# Main_Circuit.net
KiCad netlist of a schematic drawn in EAGLE
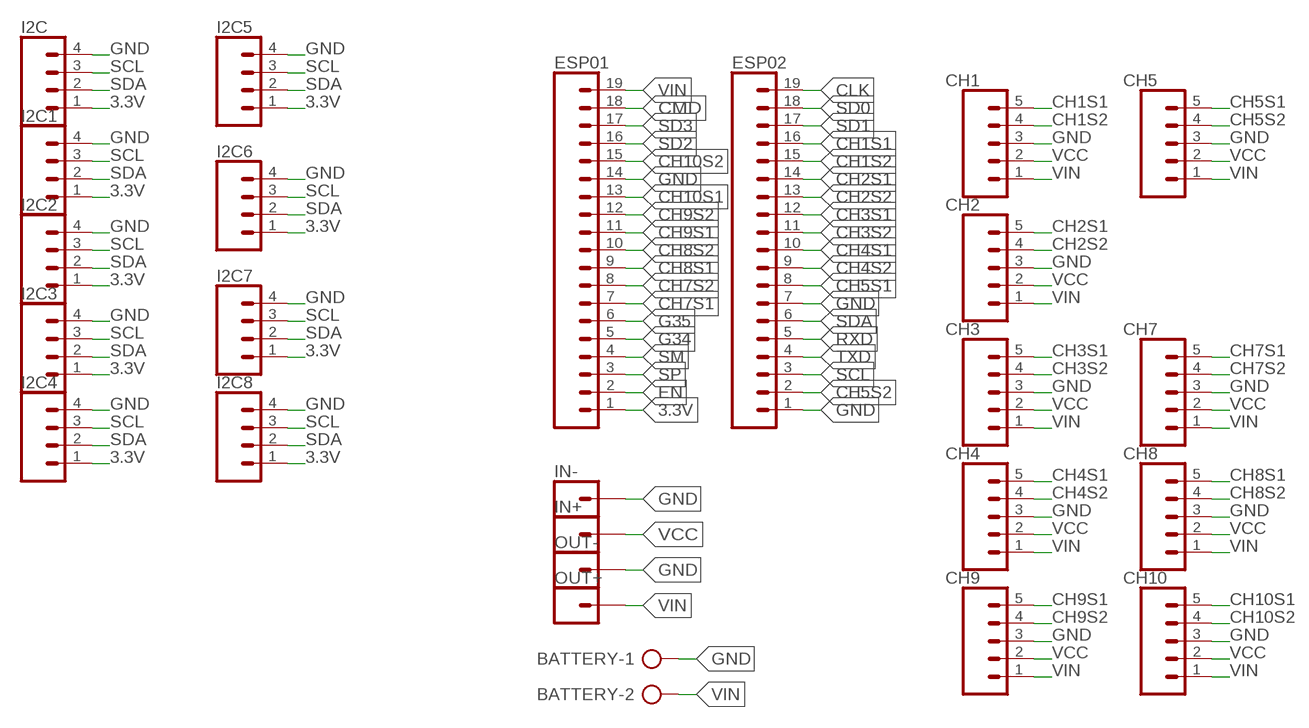
[diagram p0: schematic, sheet 1]

(export (version "E")
  (design (tool "Eeschema 10.0.6"))
  (components
    (comp (ref "BATTERY")
      (value "AK500/2-H")
      (footprint "eagle-import:AK500_2-H")
      (libsource (lib "eagle-import") (part "AK500/2-H"))
    )
    (comp (ref "CH1")
      (value "CONN_05")
      (footprint "eagle-import:1X05")
      (libsource (lib "eagle-import") (part "CONN_05"))
    )
    (comp (ref "CH2")
      (value "CONN_05")
      (footprint "eagle-import:1X05")
      (libsource (lib "eagle-import") (part "CONN_05"))
    )
    (comp (ref "CH3")
      (value "CONN_05")
      (footprint "eagle-import:1X05")
      (libsource (lib "eagle-import") (part "CONN_05"))
    )
    (comp (ref "CH4")
      (value "CONN_05")
      (footprint "eagle-import:1X05")
      (libsource (lib "eagle-import") (part "CONN_05"))
    )
    (comp (ref "CH5")
      (value "CONN_05")
      (footprint "eagle-import:1X05")
      (libsource (lib "eagle-import") (part "CONN_05"))
    )
    (comp (ref "CH7")
      (value "CONN_05")
      (footprint "eagle-import:1X05")
      (libsource (lib "eagle-import") (part "CONN_05"))
    )
    (comp (ref "CH8")
      (value "CONN_05")
      (footprint "eagle-import:1X05")
      (libsource (lib "eagle-import") (part "CONN_05"))
    )
    (comp (ref "CH9")
      (value "CONN_05")
      (footprint "eagle-import:1X05")
      (libsource (lib "eagle-import") (part "CONN_05"))
    )
    (comp (ref "CH10")
      (value "CONN_05")
      (footprint "eagle-import:1X05")
      (libsource (lib "eagle-import") (part "CONN_05"))
    )
    (comp (ref "ESP01")
      (value "CONN_19")
      (footprint "eagle-import:1X19")
      (libsource (lib "eagle-import") (part "CONN_19"))
    )
    (comp (ref "ESP02")
      (value "CONN_19")
      (footprint "eagle-import:1X19")
      (libsource (lib "eagle-import") (part "CONN_19"))
    )
    (comp (ref "I2C")
      (value "CONN_04")
      (footprint "eagle-import:1X04")
      (libsource (lib "eagle-import") (part "CONN_04"))
    )
    (comp (ref "I2C1")
      (value "CONN_04")
      (footprint "eagle-import:1X04")
      (libsource (lib "eagle-import") (part "CONN_04"))
    )
    (comp (ref "I2C2")
      (value "CONN_04")
      (footprint "eagle-import:1X04")
      (libsource (lib "eagle-import") (part "CONN_04"))
    )
    (comp (ref "I2C3")
      (value "CONN_04")
      (footprint "eagle-import:1X04")
      (libsource (lib "eagle-import") (part "CONN_04"))
    )
    (comp (ref "I2C4")
      (value "CONN_04")
      (footprint "eagle-import:1X04")
      (libsource (lib "eagle-import") (part "CONN_04"))
    )
    (comp (ref "I2C5")
      (value "CONN_04")
      (footprint "eagle-import:1X04")
      (libsource (lib "eagle-import") (part "CONN_04"))
    )
    (comp (ref "I2C6")
      (value "CONN_04")
      (footprint "eagle-import:1X04")
      (libsource (lib "eagle-import") (part "CONN_04"))
    )
    (comp (ref "I2C7")
      (value "CONN_04")
      (footprint "eagle-import:1X04")
      (libsource (lib "eagle-import") (part "CONN_04"))
    )
    (comp (ref "I2C8")
      (value "CONN_04")
      (footprint "eagle-import:1X04")
      (libsource (lib "eagle-import") (part "CONN_04"))
    )
    (comp (ref "IN+")
      (value "CONN_01")
      (footprint "eagle-import:1X01")
      (libsource (lib "eagle-import") (part "CONN_01"))
    )
    (comp (ref "IN-")
      (value "CONN_01")
      (footprint "eagle-import:1X01")
      (libsource (lib "eagle-import") (part "CONN_01"))
    )
    (comp (ref "OUT+")
      (value "CONN_01")
      (footprint "eagle-import:1X01")
      (libsource (lib "eagle-import") (part "CONN_01"))
    )
    (comp (ref "OUT-")
      (value "CONN_01")
      (footprint "eagle-import:1X01")
      (libsource (lib "eagle-import") (part "CONN_01"))
    )
  )
  (nets
    (net (code "1") (name "3.3V") (class "Default")
      (node (ref "ESP01") (pin "1") (pinfunction "1_1") (pintype "passive"))
      (node (ref "I2C") (pin "1") (pinfunction "1_1") (pintype "passive"))
      (node (ref "I2C1") (pin "1") (pinfunction "1_1") (pintype "passive"))
      (node (ref "I2C2") (pin "1") (pinfunction "1_1") (pintype "passive"))
      (node (ref "I2C3") (pin "1") (pinfunction "1_1") (pintype "passive"))
      (node (ref "I2C4") (pin "1") (pinfunction "1_1") (pintype "passive"))
      (node (ref "I2C5") (pin "1") (pinfunction "1_1") (pintype "passive"))
      (node (ref "I2C6") (pin "1") (pinfunction "1_1") (pintype "passive"))
      (node (ref "I2C7") (pin "1") (pinfunction "1_1") (pintype "passive"))
      (node (ref "I2C8") (pin "1") (pinfunction "1_1") (pintype "passive"))
    )
    (net (code "2") (name "CH1S1") (class "Default")
      (node (ref "CH1") (pin "5") (pinfunction "5_5") (pintype "passive"))
      (node (ref "ESP02") (pin "16") (pinfunction "16_16") (pintype "passive"))
    )
    (net (code "3") (name "CH1S2") (class "Default")
      (node (ref "CH1") (pin "4") (pinfunction "4_4") (pintype "passive"))
      (node (ref "ESP02") (pin "15") (pinfunction "15_15") (pintype "passive"))
    )
    (net (code "4") (name "CH2S1") (class "Default")
      (node (ref "CH2") (pin "5") (pinfunction "5_5") (pintype "passive"))
      (node (ref "ESP02") (pin "14") (pinfunction "14_14") (pintype "passive"))
    )
    (net (code "5") (name "CH2S2") (class "Default")
      (node (ref "CH2") (pin "4") (pinfunction "4_4") (pintype "passive"))
      (node (ref "ESP02") (pin "13") (pinfunction "13_13") (pintype "passive"))
    )
    (net (code "6") (name "CH3S1") (class "Default")
      (node (ref "CH3") (pin "5") (pinfunction "5_5") (pintype "passive"))
      (node (ref "ESP02") (pin "12") (pinfunction "12_12") (pintype "passive"))
    )
    (net (code "7") (name "CH3S2") (class "Default")
      (node (ref "CH3") (pin "4") (pinfunction "4_4") (pintype "passive"))
      (node (ref "ESP02") (pin "11") (pinfunction "11_11") (pintype "passive"))
    )
    (net (code "8") (name "CH4S1") (class "Default")
      (node (ref "CH4") (pin "5") (pinfunction "5_5") (pintype "passive"))
      (node (ref "ESP02") (pin "10") (pinfunction "10_10") (pintype "passive"))
    )
    (net (code "9") (name "CH4S2") (class "Default")
      (node (ref "CH4") (pin "4") (pinfunction "4_4") (pintype "passive"))
      (node (ref "ESP02") (pin "9") (pinfunction "9_9") (pintype "passive"))
    )
    (net (code "10") (name "CH5S1") (class "Default")
      (node (ref "CH5") (pin "5") (pinfunction "5_5") (pintype "passive"))
      (node (ref "ESP02") (pin "8") (pinfunction "8_8") (pintype "passive"))
    )
    (net (code "11") (name "CH5S2") (class "Default")
      (node (ref "CH5") (pin "4") (pinfunction "4_4") (pintype "passive"))
      (node (ref "ESP02") (pin "2") (pinfunction "2_2") (pintype "passive"))
    )
    (net (code "12") (name "CH7S1") (class "Default")
      (node (ref "CH7") (pin "5") (pinfunction "5_5") (pintype "passive"))
      (node (ref "ESP01") (pin "7") (pinfunction "7_7") (pintype "passive"))
    )
    (net (code "13") (name "CH7S2") (class "Default")
      (node (ref "CH7") (pin "4") (pinfunction "4_4") (pintype "passive"))
      (node (ref "ESP01") (pin "8") (pinfunction "8_8") (pintype "passive"))
    )
    (net (code "14") (name "CH8S1") (class "Default")
      (node (ref "CH8") (pin "5") (pinfunction "5_5") (pintype "passive"))
      (node (ref "ESP01") (pin "9") (pinfunction "9_9") (pintype "passive"))
    )
    (net (code "15") (name "CH8S2") (class "Default")
      (node (ref "CH8") (pin "4") (pinfunction "4_4") (pintype "passive"))
      (node (ref "ESP01") (pin "10") (pinfunction "10_10") (pintype "passive"))
    )
    (net (code "16") (name "CH9S1") (class "Default")
      (node (ref "CH9") (pin "5") (pinfunction "5_5") (pintype "passive"))
      (node (ref "ESP01") (pin "11") (pinfunction "11_11") (pintype "passive"))
    )
    (net (code "17") (name "CH9S2") (class "Default")
      (node (ref "CH9") (pin "4") (pinfunction "4_4") (pintype "passive"))
      (node (ref "ESP01") (pin "12") (pinfunction "12_12") (pintype "passive"))
    )
    (net (code "18") (name "CH10S1") (class "Default")
      (node (ref "CH10") (pin "5") (pinfunction "5_5") (pintype "passive"))
      (node (ref "ESP01") (pin "13") (pinfunction "13_13") (pintype "passive"))
    )
    (net (code "19") (name "CH10S2") (class "Default")
      (node (ref "CH10") (pin "4") (pinfunction "4_4") (pintype "passive"))
      (node (ref "ESP01") (pin "15") (pinfunction "15_15") (pintype "passive"))
    )
    (net (code "20") (name "CLK") (class "Default")
      (node (ref "ESP02") (pin "19") (pinfunction "19_19") (pintype "passive"))
    )
    (net (code "21") (name "CMD") (class "Default")
      (node (ref "ESP01") (pin "18") (pinfunction "18_18") (pintype "passive"))
    )
    (net (code "22") (name "EN") (class "Default")
      (node (ref "ESP01") (pin "2") (pinfunction "2_2") (pintype "passive"))
    )
    (net (code "23") (name "G34") (class "Default")
      (node (ref "ESP01") (pin "5") (pinfunction "5_5") (pintype "passive"))
    )
    (net (code "24") (name "G35") (class "Default")
      (node (ref "ESP01") (pin "6") (pinfunction "6_6") (pintype "passive"))
    )
    (net (code "25") (name "GND") (class "Default")
      (node (ref "BATTERY") (pin "1") (pinfunction "KL_1") (pintype "passive"))
      (node (ref "CH1") (pin "3") (pinfunction "3_3") (pintype "passive"))
      (node (ref "CH10") (pin "3") (pinfunction "3_3") (pintype "passive"))
      (node (ref "CH2") (pin "3") (pinfunction "3_3") (pintype "passive"))
      (node (ref "CH3") (pin "3") (pinfunction "3_3") (pintype "passive"))
      (node (ref "CH4") (pin "3") (pinfunction "3_3") (pintype "passive"))
      (node (ref "CH5") (pin "3") (pinfunction "3_3") (pintype "passive"))
      (node (ref "CH7") (pin "3") (pinfunction "3_3") (pintype "passive"))
      (node (ref "CH8") (pin "3") (pinfunction "3_3") (pintype "passive"))
      (node (ref "CH9") (pin "3") (pinfunction "3_3") (pintype "passive"))
      (node (ref "ESP01") (pin "14") (pinfunction "14_14") (pintype "passive"))
      (node (ref "ESP02") (pin "1") (pinfunction "1_1") (pintype "passive"))
      (node (ref "ESP02") (pin "7") (pinfunction "7_7") (pintype "passive"))
      (node (ref "I2C") (pin "4") (pinfunction "4_4") (pintype "passive"))
      (node (ref "I2C1") (pin "4") (pinfunction "4_4") (pintype "passive"))
      (node (ref "I2C2") (pin "4") (pinfunction "4_4") (pintype "passive"))
      (node (ref "I2C3") (pin "4") (pinfunction "4_4") (pintype "passive"))
      (node (ref "I2C4") (pin "4") (pinfunction "4_4") (pintype "passive"))
      (node (ref "I2C5") (pin "4") (pinfunction "4_4") (pintype "passive"))
      (node (ref "I2C6") (pin "4") (pinfunction "4_4") (pintype "passive"))
      (node (ref "I2C7") (pin "4") (pinfunction "4_4") (pintype "passive"))
      (node (ref "I2C8") (pin "4") (pinfunction "4_4") (pintype "passive"))
      (node (ref "IN-") (pin "1") (pinfunction "1_1") (pintype "passive"))
      (node (ref "OUT-") (pin "1") (pinfunction "1_1") (pintype "passive"))
    )
    (net (code "26") (name "RXD") (class "Default")
      (node (ref "ESP02") (pin "5") (pinfunction "5_5") (pintype "passive"))
    )
    (net (code "27") (name "SCL") (class "Default")
      (node (ref "ESP02") (pin "3") (pinfunction "3_3") (pintype "passive"))
      (node (ref "I2C") (pin "3") (pinfunction "3_3") (pintype "passive"))
      (node (ref "I2C1") (pin "3") (pinfunction "3_3") (pintype "passive"))
      (node (ref "I2C2") (pin "3") (pinfunction "3_3") (pintype "passive"))
      (node (ref "I2C3") (pin "3") (pinfunction "3_3") (pintype "passive"))
      (node (ref "I2C4") (pin "3") (pinfunction "3_3") (pintype "passive"))
      (node (ref "I2C5") (pin "3") (pinfunction "3_3") (pintype "passive"))
      (node (ref "I2C6") (pin "3") (pinfunction "3_3") (pintype "passive"))
      (node (ref "I2C7") (pin "3") (pinfunction "3_3") (pintype "passive"))
      (node (ref "I2C8") (pin "3") (pinfunction "3_3") (pintype "passive"))
    )
    (net (code "28") (name "SD0") (class "Default")
      (node (ref "ESP02") (pin "18") (pinfunction "18_18") (pintype "passive"))
    )
    (net (code "29") (name "SD1") (class "Default")
      (node (ref "ESP02") (pin "17") (pinfunction "17_17") (pintype "passive"))
    )
    (net (code "30") (name "SD2") (class "Default")
      (node (ref "ESP01") (pin "16") (pinfunction "16_16") (pintype "passive"))
    )
    (net (code "31") (name "SD3") (class "Default")
      (node (ref "ESP01") (pin "17") (pinfunction "17_17") (pintype "passive"))
    )
    (net (code "32") (name "SDA") (class "Default")
      (node (ref "ESP02") (pin "6") (pinfunction "6_6") (pintype "passive"))
      (node (ref "I2C") (pin "2") (pinfunction "2_2") (pintype "passive"))
      (node (ref "I2C1") (pin "2") (pinfunction "2_2") (pintype "passive"))
      (node (ref "I2C2") (pin "2") (pinfunction "2_2") (pintype "passive"))
      (node (ref "I2C3") (pin "2") (pinfunction "2_2") (pintype "passive"))
      (node (ref "I2C4") (pin "2") (pinfunction "2_2") (pintype "passive"))
      (node (ref "I2C5") (pin "2") (pinfunction "2_2") (pintype "passive"))
      (node (ref "I2C6") (pin "2") (pinfunction "2_2") (pintype "passive"))
      (node (ref "I2C7") (pin "2") (pinfunction "2_2") (pintype "passive"))
      (node (ref "I2C8") (pin "2") (pinfunction "2_2") (pintype "passive"))
    )
    (net (code "33") (name "SM") (class "Default")
      (node (ref "ESP01") (pin "4") (pinfunction "4_4") (pintype "passive"))
    )
    (net (code "34") (name "SP") (class "Default")
      (node (ref "ESP01") (pin "3") (pinfunction "3_3") (pintype "passive"))
    )
    (net (code "35") (name "TXD") (class "Default")
      (node (ref "ESP02") (pin "4") (pinfunction "4_4") (pintype "passive"))
    )
    (net (code "36") (name "VCC") (class "Default")
      (node (ref "CH1") (pin "2") (pinfunction "2_2") (pintype "passive"))
      (node (ref "CH10") (pin "2") (pinfunction "2_2") (pintype "passive"))
      (node (ref "CH2") (pin "2") (pinfunction "2_2") (pintype "passive"))
      (node (ref "CH3") (pin "2") (pinfunction "2_2") (pintype "passive"))
      (node (ref "CH4") (pin "2") (pinfunction "2_2") (pintype "passive"))
      (node (ref "CH5") (pin "2") (pinfunction "2_2") (pintype "passive"))
      (node (ref "CH7") (pin "2") (pinfunction "2_2") (pintype "passive"))
      (node (ref "CH8") (pin "2") (pinfunction "2_2") (pintype "passive"))
      (node (ref "CH9") (pin "2") (pinfunction "2_2") (pintype "passive"))
      (node (ref "IN+") (pin "1") (pinfunction "1_1") (pintype "passive"))
    )
    (net (code "37") (name "VIN") (class "Default")
      (node (ref "BATTERY") (pin "2") (pinfunction "KL_2") (pintype "passive"))
      (node (ref "CH1") (pin "1") (pinfunction "1_1") (pintype "passive"))
      (node (ref "CH10") (pin "1") (pinfunction "1_1") (pintype "passive"))
      (node (ref "CH2") (pin "1") (pinfunction "1_1") (pintype "passive"))
      (node (ref "CH3") (pin "1") (pinfunction "1_1") (pintype "passive"))
      (node (ref "CH4") (pin "1") (pinfunction "1_1") (pintype "passive"))
      (node (ref "CH5") (pin "1") (pinfunction "1_1") (pintype "passive"))
      (node (ref "CH7") (pin "1") (pinfunction "1_1") (pintype "passive"))
      (node (ref "CH8") (pin "1") (pinfunction "1_1") (pintype "passive"))
      (node (ref "CH9") (pin "1") (pinfunction "1_1") (pintype "passive"))
      (node (ref "ESP01") (pin "19") (pinfunction "19_19") (pintype "passive"))
      (node (ref "OUT+") (pin "1") (pinfunction "1_1") (pintype "passive"))
    )
  )
)
